# PCB.net
KiCad netlist of a schematic drawn in EasyEDA Pro
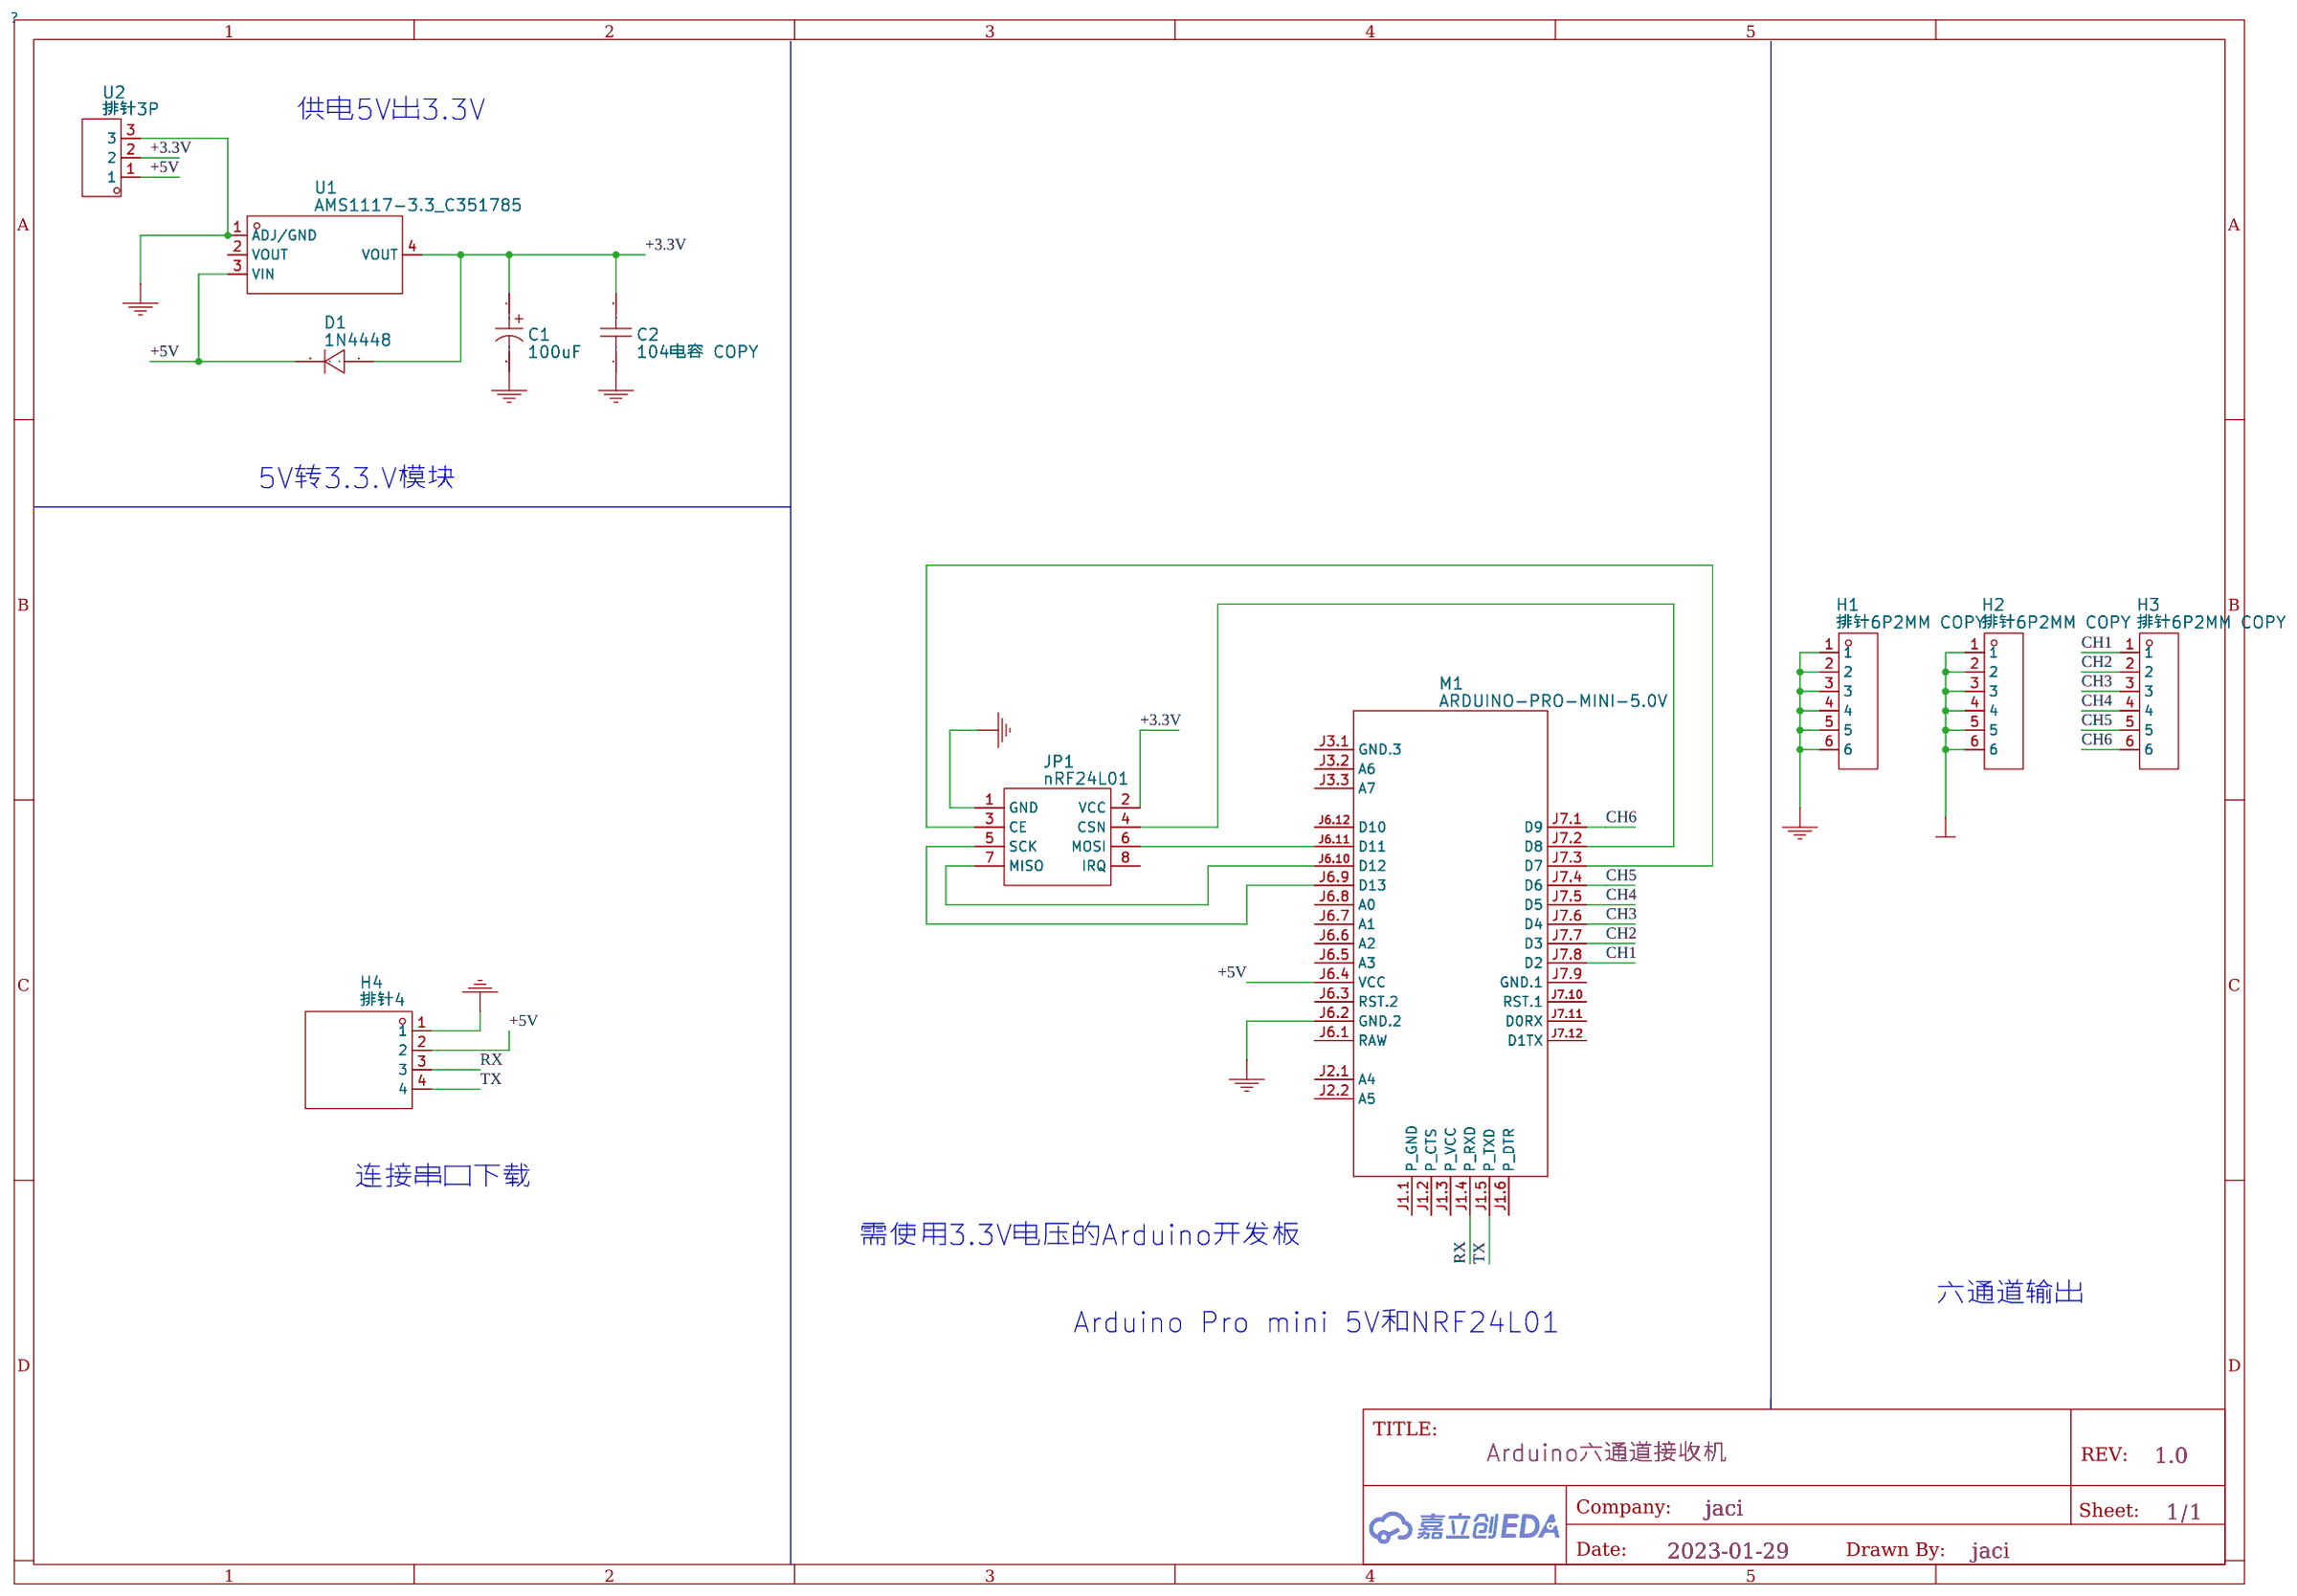
[diagram p0: schematic sheet]

(export (version "E")
  (design (tool "Eeschema 10.0.6"))
  (components
    (comp (ref "C1")
      (value "100uF")
      (fields (field (name "Manufacturer Part") "ECA1HHG101") (field (name "Manufacturer") "PANASONIC(松下)"))
      (libsource (lib "easyedapro") (part "100uF"))
    )
    (comp (ref "C2") (value "104电容 COPY") (libsource (lib "easyedapro") (part "104电容 COPY")))
    (comp (ref "D1")
      (value "1N4448")
      (fields (field (name "Manufacturer") "SEMTECH"))
      (libsource (lib "easyedapro") (part "1N4448"))
    )
    (comp (ref "H1") (value "排针6P2MM COPY") (libsource (lib "easyedapro") (part "排针6P2MM COPY")))
    (comp (ref "H2") (value "排针6P2MM COPY") (libsource (lib "easyedapro") (part "排针6P2MM COPY")))
    (comp (ref "H3") (value "排针6P2MM COPY") (libsource (lib "easyedapro") (part "排针6P2MM COPY")))
    (comp (ref "H4")
      (value "排针4")
      (fields
        (field (name "Manufacturer Part") "A2541WV-10P")
        (field (name "Manufacturer") "ChangjiangConnectors")
      )
      (libsource (lib "easyedapro") (part "排针4"))
    )
    (comp (ref "JP1")
      (value "nRF24L01")
      (fields (field (name "版权归属") "源创客"))
      (libsource (lib "easyedapro") (part "nRF24L01"))
    )
    (comp (ref "M1")
      (value "ARDUINO-PRO-MINI-5.0V")
      (libsource (lib "easyedapro") (part "ARDUINO-PRO-MINI-5.0V"))
    )
    (comp (ref "U1")
      (value "AMS1117-3.3_C351785")
      (fields (field (name "Manufacturer Part") "AMS1117-3.3") (field (name "Manufacturer") "PUOLOP(迪浦)"))
      (libsource (lib "easyedapro") (part "AMS1117-3.3_C351785"))
    )
    (comp (ref "U2") (value "排针3P") (libsource (lib "easyedapro") (part "排针3P")))
  )
  (nets
    (net (code "1") (name "+5V") (class "Default")
      (node (ref "D1") (pin "2") (pinfunction "K_2") (pintype "input"))
      (node (ref "H2") (pin "1") (pinfunction "1_1") (pintype "input"))
      (node (ref "H2") (pin "2") (pinfunction "2_2") (pintype "input"))
      (node (ref "H2") (pin "3") (pinfunction "3_3") (pintype "input"))
      (node (ref "H2") (pin "4") (pinfunction "4_4") (pintype "input"))
      (node (ref "H2") (pin "5") (pinfunction "5_5") (pintype "input"))
      (node (ref "H2") (pin "6") (pinfunction "6_6") (pintype "input"))
      (node (ref "H4") (pin "2") (pinfunction "2_2") (pintype "input"))
      (node (ref "M1") (pin "J6.4") (pinfunction "VCC_J6.4") (pintype "input"))
      (node (ref "U1") (pin "3") (pinfunction "VIN_3") (pintype "input"))
      (node (ref "U2") (pin "1") (pinfunction "1_1") (pintype "input"))
    )
    (net (code "2") (name "/+3.3V") (class "Default")
      (node (ref "C1") (pin "1") (pinfunction "1_1") (pintype "input"))
      (node (ref "C2") (pin "2") (pinfunction "2_2") (pintype "input"))
      (node (ref "D1") (pin "1") (pinfunction "A_1") (pintype "input"))
      (node (ref "JP1") (pin "2") (pinfunction "VCC_2") (pintype "input"))
      (node (ref "U1") (pin "4") (pinfunction "VOUT_4") (pintype "input"))
      (node (ref "U2") (pin "2") (pinfunction "2_2") (pintype "input"))
    )
    (net (code "3") (name "/CH1") (class "Default")
      (node (ref "H3") (pin "1") (pinfunction "1_1") (pintype "input"))
      (node (ref "M1") (pin "J7.8") (pinfunction "D2_J7.8") (pintype "input"))
    )
    (net (code "4") (name "/CH2") (class "Default")
      (node (ref "H3") (pin "2") (pinfunction "2_2") (pintype "input"))
      (node (ref "M1") (pin "J7.7") (pinfunction "D3_J7.7") (pintype "input"))
    )
    (net (code "5") (name "/CH3") (class "Default")
      (node (ref "H3") (pin "3") (pinfunction "3_3") (pintype "input"))
      (node (ref "M1") (pin "J7.6") (pinfunction "D4_J7.6") (pintype "input"))
    )
    (net (code "6") (name "/CH4") (class "Default")
      (node (ref "H3") (pin "4") (pinfunction "4_4") (pintype "input"))
      (node (ref "M1") (pin "J7.5") (pinfunction "D5_J7.5") (pintype "input"))
    )
    (net (code "7") (name "/CH5") (class "Default")
      (node (ref "H3") (pin "5") (pinfunction "5_5") (pintype "input"))
      (node (ref "M1") (pin "J7.4") (pinfunction "D6_J7.4") (pintype "input"))
    )
    (net (code "8") (name "/CH6") (class "Default")
      (node (ref "H3") (pin "6") (pinfunction "6_6") (pintype "input"))
      (node (ref "M1") (pin "J7.1") (pinfunction "D9_J7.1") (pintype "input"))
    )
    (net (code "9") (name "/RX") (class "Default")
      (node (ref "H4") (pin "3") (pinfunction "3_3") (pintype "input"))
      (node (ref "M1") (pin "J1.4") (pinfunction "P_RXD_J1.4") (pintype "input"))
    )
    (net (code "10") (name "/TX") (class "Default")
      (node (ref "H4") (pin "4") (pinfunction "4_4") (pintype "input"))
      (node (ref "M1") (pin "J1.5") (pinfunction "P_TXD_J1.5") (pintype "input"))
    )
    (net (code "11") (name "GND") (class "Default")
      (node (ref "C1") (pin "2") (pinfunction "2_2") (pintype "input"))
      (node (ref "C2") (pin "1") (pinfunction "1_1") (pintype "input"))
      (node (ref "H1") (pin "1") (pinfunction "1_1") (pintype "input"))
      (node (ref "H1") (pin "2") (pinfunction "2_2") (pintype "input"))
      (node (ref "H1") (pin "3") (pinfunction "3_3") (pintype "input"))
      (node (ref "H1") (pin "4") (pinfunction "4_4") (pintype "input"))
      (node (ref "H1") (pin "5") (pinfunction "5_5") (pintype "input"))
      (node (ref "H1") (pin "6") (pinfunction "6_6") (pintype "input"))
      (node (ref "H4") (pin "1") (pinfunction "1_1") (pintype "input"))
      (node (ref "JP1") (pin "1") (pinfunction "GND_1") (pintype "input"))
      (node (ref "M1") (pin "J6.2") (pinfunction "GND.2_J6.2") (pintype "input"))
      (node (ref "U1") (pin "1") (pinfunction "ADJ/GND_1") (pintype "input"))
      (node (ref "U2") (pin "3") (pinfunction "3_3") (pintype "input"))
    )
    (net (code "12") (name "Net-(JP1-CE)") (class "Default")
      (node (ref "JP1") (pin "3") (pinfunction "CE_3") (pintype "input"))
      (node (ref "M1") (pin "J7.3") (pinfunction "D7_J7.3") (pintype "input"))
    )
    (net (code "13") (name "Net-(JP1-CSN)") (class "Default")
      (node (ref "JP1") (pin "4") (pinfunction "CSN_4") (pintype "input"))
      (node (ref "M1") (pin "J7.2") (pinfunction "D8_J7.2") (pintype "input"))
    )
    (net (code "14") (name "Net-(JP1-MISO)") (class "Default")
      (node (ref "JP1") (pin "7") (pinfunction "MISO_7") (pintype "input"))
      (node (ref "M1") (pin "J6.10") (pinfunction "D12_J6.10") (pintype "input"))
    )
    (net (code "15") (name "Net-(JP1-MOSI)") (class "Default")
      (node (ref "JP1") (pin "6") (pinfunction "MOSI_6") (pintype "input"))
      (node (ref "M1") (pin "J6.11") (pinfunction "D11_J6.11") (pintype "input"))
    )
    (net (code "16") (name "Net-(JP1-SCK)") (class "Default")
      (node (ref "JP1") (pin "5") (pinfunction "SCK_5") (pintype "input"))
      (node (ref "M1") (pin "J6.9") (pinfunction "D13_J6.9") (pintype "input"))
    )
    (net (code "17") (name "unconnected-(JP1-IRQ-Pad8)") (class "Default")
      (node (ref "JP1") (pin "8") (pinfunction "IRQ_8") (pintype "input"))
    )
    (net (code "18") (name "unconnected-(M1-A0-PadJ6.8)") (class "Default")
      (node (ref "M1") (pin "J6.8") (pinfunction "A0_J6.8") (pintype "input"))
    )
    (net (code "19") (name "unconnected-(M1-A1-PadJ6.7)") (class "Default")
      (node (ref "M1") (pin "J6.7") (pinfunction "A1_J6.7") (pintype "input"))
    )
    (net (code "20") (name "unconnected-(M1-A2-PadJ6.6)") (class "Default")
      (node (ref "M1") (pin "J6.6") (pinfunction "A2_J6.6") (pintype "input"))
    )
    (net (code "21") (name "unconnected-(M1-A3-PadJ6.5)") (class "Default")
      (node (ref "M1") (pin "J6.5") (pinfunction "A3_J6.5") (pintype "input"))
    )
    (net (code "22") (name "unconnected-(M1-A4-PadJ2.1)") (class "Default")
      (node (ref "M1") (pin "J2.1") (pinfunction "A4_J2.1") (pintype "input"))
    )
    (net (code "23") (name "unconnected-(M1-A5-PadJ2.2)") (class "Default")
      (node (ref "M1") (pin "J2.2") (pinfunction "A5_J2.2") (pintype "input"))
    )
    (net (code "24") (name "unconnected-(M1-A6-PadJ3.2)") (class "Default")
      (node (ref "M1") (pin "J3.2") (pinfunction "A6_J3.2") (pintype "input"))
    )
    (net (code "25") (name "unconnected-(M1-A7-PadJ3.3)") (class "Default")
      (node (ref "M1") (pin "J3.3") (pinfunction "A7_J3.3") (pintype "input"))
    )
    (net (code "26") (name "unconnected-(M1-D0RX-PadJ7.11)") (class "Default")
      (node (ref "M1") (pin "J7.11") (pinfunction "D0RX_J7.11") (pintype "input"))
    )
    (net (code "27") (name "unconnected-(M1-D1TX-PadJ7.12)") (class "Default")
      (node (ref "M1") (pin "J7.12") (pinfunction "D1TX_J7.12") (pintype "input"))
    )
    (net (code "28") (name "unconnected-(M1-D10-PadJ6.12)") (class "Default")
      (node (ref "M1") (pin "J6.12") (pinfunction "D10_J6.12") (pintype "input"))
    )
    (net (code "29") (name "unconnected-(M1-GND.1-PadJ7.9)") (class "Default")
      (node (ref "M1") (pin "J7.9") (pinfunction "GND.1_J7.9") (pintype "input"))
    )
    (net (code "30") (name "unconnected-(M1-GND.3-PadJ3.1)") (class "Default")
      (node (ref "M1") (pin "J3.1") (pinfunction "GND.3_J3.1") (pintype "input"))
    )
    (net (code "31") (name "unconnected-(M1-P_CTS-PadJ1.2)") (class "Default")
      (node (ref "M1") (pin "J1.2") (pinfunction "P_CTS_J1.2") (pintype "input"))
    )
    (net (code "32") (name "unconnected-(M1-P_DTR-PadJ1.6)") (class "Default")
      (node (ref "M1") (pin "J1.6") (pinfunction "P_DTR_J1.6") (pintype "input"))
    )
    (net (code "33") (name "unconnected-(M1-P_GND-PadJ1.1)") (class "Default")
      (node (ref "M1") (pin "J1.1") (pinfunction "P_GND_J1.1") (pintype "input"))
    )
    (net (code "34") (name "unconnected-(M1-P_VCC-PadJ1.3)") (class "Default")
      (node (ref "M1") (pin "J1.3") (pinfunction "P_VCC_J1.3") (pintype "input"))
    )
    (net (code "35") (name "unconnected-(M1-RAW-PadJ6.1)") (class "Default")
      (node (ref "M1") (pin "J6.1") (pinfunction "RAW_J6.1") (pintype "input"))
    )
    (net (code "36") (name "unconnected-(M1-RST.1-PadJ7.10)") (class "Default")
      (node (ref "M1") (pin "J7.10") (pinfunction "RST.1_J7.10") (pintype "input"))
    )
    (net (code "37") (name "unconnected-(M1-RST.2-PadJ6.3)") (class "Default")
      (node (ref "M1") (pin "J6.3") (pinfunction "RST.2_J6.3") (pintype "input"))
    )
    (net (code "38") (name "unconnected-(U1-VOUT-Pad2)") (class "Default")
      (node (ref "U1") (pin "2") (pinfunction "VOUT_2") (pintype "input"))
    )
  )
)
